# design.net
KiCad netlist of a schematic drawn in Altium Designer
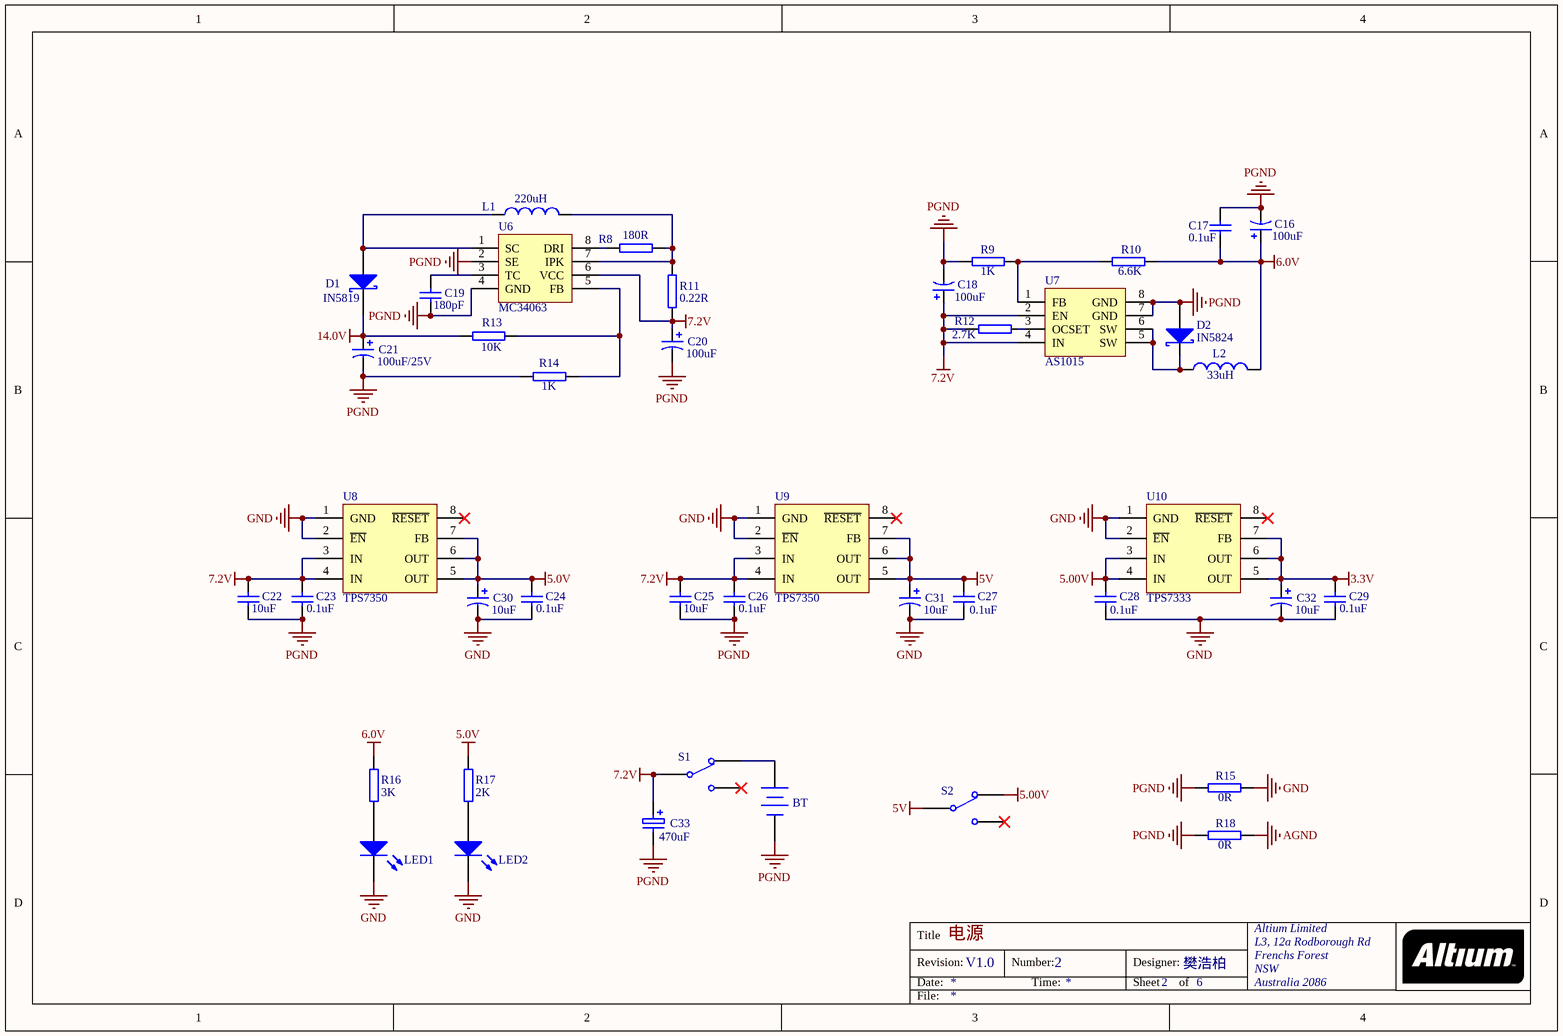
[diagram p0: 电源.SchDoc]

(export (version "E")
  (design (tool "Eeschema 10.0.6"))
  (components
    (comp (ref "BT")
      (value "Battery")
      (footprint "Header-5.0-SMD")
      (libsource (lib "Connectors") (part "Battery"))
    )
    (comp (ref "C16")
      (value "100uF")
      (footprint "CASE-C_6032-28")
      (libsource (lib "Connectors") (part "Cap-Pol_1"))
    )
    (comp (ref "C17") (value "0.1uF") (footprint "CAP-0603") (libsource (lib "Connectors") (part "Cap")))
    (comp (ref "C18")
      (value "100uF")
      (footprint "CASE-C_6032-28")
      (libsource (lib "Connectors") (part "Cap-Pol_1"))
    )
    (comp (ref "C19") (value "180pF") (footprint "CAP-0603") (libsource (lib "Connectors") (part "Cap")))
    (comp (ref "C20")
      (value "100uF")
      (footprint "CASE-C_6032-28")
      (libsource (lib "Connectors") (part "Cap-Pol_1"))
    )
    (comp (ref "C21")
      (value "100uF/25V")
      (footprint "CASE-D_7343-31")
      (libsource (lib "Connectors") (part "Cap-Pol_1"))
    )
    (comp (ref "C22") (value "10uF") (footprint "CAP-0603") (libsource (lib "Connectors") (part "Cap")))
    (comp (ref "C23") (value "0.1uF") (footprint "CAP-0603") (libsource (lib "Connectors") (part "Cap")))
    (comp (ref "C24") (value "0.1uF") (footprint "CAP-0603") (libsource (lib "Connectors") (part "Cap")))
    (comp (ref "C25") (value "10uF") (footprint "CAP-0603") (libsource (lib "Connectors") (part "Cap")))
    (comp (ref "C26") (value "0.1uF") (footprint "CAP-0603") (libsource (lib "Connectors") (part "Cap")))
    (comp (ref "C27") (value "0.1uF") (footprint "CAP-0603") (libsource (lib "Connectors") (part "Cap")))
    (comp (ref "C28") (value "0.1uF") (footprint "CAP-0603") (libsource (lib "Connectors") (part "Cap")))
    (comp (ref "C29") (value "0.1uF") (footprint "CAP-0603") (libsource (lib "Connectors") (part "Cap")))
    (comp (ref "C30")
      (value "10uF")
      (footprint "CASE-A_3216-18")
      (libsource (lib "Connectors") (part "Cap-Pol_1"))
    )
    (comp (ref "C31")
      (value "10uF")
      (footprint "CASE-A_3216-18")
      (libsource (lib "Connectors") (part "Cap-Pol_1"))
    )
    (comp (ref "C32")
      (value "10uF")
      (footprint "CASE-A_3216-18")
      (libsource (lib "Connectors") (part "Cap-Pol_1"))
    )
    (comp (ref "C33")
      (value "470uF")
      (footprint "CAP-ALU-F_8.0x8.3x10.2")
      (libsource (lib "Connectors") (part "Cap-Pol_2"))
    )
    (comp (ref "D1")
      (value "IN5819")
      (footprint "Diode-SMD-SOD-123")
      (libsource (lib "Connectors") (part "Diode-Schottky"))
    )
    (comp (ref "D2")
      (value "IN5824")
      (footprint "Diode-SMD-SMA")
      (libsource (lib "Connectors") (part "Diode-Schottky"))
    )
    (comp (ref "L1")
      (value "220uH")
      (footprint "Inductor-CD-54")
      (libsource (lib "Connectors") (part "Inductor"))
    )
    (comp (ref "L2")
      (value "33uH")
      (footprint "Inductor-CD-54")
      (libsource (lib "Connectors") (part "Inductor"))
    )
    (comp (ref "LED1") (value "LED") (footprint "LED-GRE-0603") (libsource (lib "Connectors") (part "LED")))
    (comp (ref "LED2") (value "LED") (footprint "LED-BLU-0603") (libsource (lib "Connectors") (part "LED")))
    (comp (ref "R8") (value "180R") (footprint "RES-0603") (libsource (lib "Connectors") (part "Res")))
    (comp (ref "R9") (value "1K") (footprint "RES-0603") (libsource (lib "Connectors") (part "Res")))
    (comp (ref "R10") (value "6.6K") (footprint "RES-0603") (libsource (lib "Connectors") (part "Res")))
    (comp (ref "R11") (value "0.22R") (footprint "RES-0603") (libsource (lib "Connectors") (part "Res")))
    (comp (ref "R12") (value "2.7K") (footprint "RES-0603") (libsource (lib "Connectors") (part "Res")))
    (comp (ref "R13") (value "10K") (footprint "RES-0603") (libsource (lib "Connectors") (part "Res")))
    (comp (ref "R14") (value "1K") (footprint "RES-0603") (libsource (lib "Connectors") (part "Res")))
    (comp (ref "R15") (value "0R") (footprint "RES-0603") (libsource (lib "Connectors") (part "Res")))
    (comp (ref "R16") (value "3K") (footprint "RES-0603") (libsource (lib "Connectors") (part "Res")))
    (comp (ref "R17") (value "2K") (footprint "RES-0603") (libsource (lib "Connectors") (part "Res")))
    (comp (ref "R18") (value "0R") (footprint "RES-0603") (libsource (lib "Connectors") (part "Res")))
    (comp (ref "S1")
      (value "Key-3")
      (footprint "SW-3-SMTS-102")
      (libsource (lib "Connectors") (part "Key-3"))
    )
    (comp (ref "S2")
      (value "Key-3")
      (footprint "SW-3-SMTS-102")
      (libsource (lib "Connectors") (part "Key-3"))
    )
    (comp (ref "U6") (value "MC34063") (footprint "SOP-8") (libsource (lib "Devices") (part "MC34063")))
    (comp (ref "U7") (value "AS1015") (footprint "SOP-8") (libsource (lib "Devices") (part "AS1015")))
    (comp (ref "U8") (value "TPS7350") (footprint "SOP-8") (libsource (lib "Devices") (part "TPS7350")))
    (comp (ref "U9") (value "TPS7350") (footprint "SOP-8") (libsource (lib "Devices") (part "TPS7350")))
    (comp (ref "U10") (value "TPS7333") (footprint "SOP-8") (libsource (lib "Devices") (part "TPS7350")))
  )
  (nets
    (net (code "1") (name "3.3V") (class "Default")
      (node (ref "C29") (pin "2") (pinfunction "2_2") (pintype "passive"))
      (node (ref "C32") (pin "A") (pinfunction "A_A") (pintype "passive"))
      (node (ref "U10") (pin "5") (pinfunction "OUT_5") (pintype "power_in"))
      (node (ref "U10") (pin "6") (pinfunction "OUT_6") (pintype "power_in"))
      (node (ref "U10") (pin "7") (pinfunction "FB_7") (pintype "power_in"))
    )
    (net (code "2") (name "5.00V") (class "Default")
      (node (ref "C28") (pin "2") (pinfunction "2_2") (pintype "passive"))
      (node (ref "S2") (pin "3") (pinfunction "3_3") (pintype "passive"))
      (node (ref "U10") (pin "3") (pinfunction "IN_3") (pintype "power_in"))
      (node (ref "U10") (pin "4") (pinfunction "IN_4") (pintype "power_in"))
    )
    (net (code "3") (name "5.0V") (class "Default")
      (node (ref "C24") (pin "2") (pinfunction "2_2") (pintype "passive"))
      (node (ref "C30") (pin "A") (pinfunction "A_A") (pintype "passive"))
      (node (ref "R17") (pin "2") (pinfunction "2_2") (pintype "passive"))
      (node (ref "U8") (pin "5") (pinfunction "OUT_5") (pintype "power_in"))
      (node (ref "U8") (pin "6") (pinfunction "OUT_6") (pintype "power_in"))
      (node (ref "U8") (pin "7") (pinfunction "FB_7") (pintype "power_in"))
    )
    (net (code "4") (name "5V") (class "Default")
      (node (ref "C27") (pin "2") (pinfunction "2_2") (pintype "passive"))
      (node (ref "C31") (pin "A") (pinfunction "A_A") (pintype "passive"))
      (node (ref "S2") (pin "2") (pinfunction "2_2") (pintype "passive"))
      (node (ref "U9") (pin "5") (pinfunction "OUT_5") (pintype "power_in"))
      (node (ref "U9") (pin "6") (pinfunction "OUT_6") (pintype "power_in"))
      (node (ref "U9") (pin "7") (pinfunction "FB_7") (pintype "power_in"))
    )
    (net (code "5") (name "6.0V") (class "Default")
      (node (ref "C16") (pin "A") (pinfunction "A_A") (pintype "passive"))
      (node (ref "C17") (pin "1") (pinfunction "1_1") (pintype "passive"))
      (node (ref "L2") (pin "2") (pinfunction "2_2") (pintype "passive"))
      (node (ref "R10") (pin "1") (pinfunction "1_1") (pintype "passive"))
      (node (ref "R16") (pin "2") (pinfunction "2_2") (pintype "passive"))
    )
    (net (code "6") (name "7.2V") (class "Default")
      (node (ref "C18") (pin "A") (pinfunction "A_A") (pintype "passive"))
      (node (ref "C20") (pin "A") (pinfunction "A_A") (pintype "passive"))
      (node (ref "C22") (pin "2") (pinfunction "2_2") (pintype "passive"))
      (node (ref "C23") (pin "2") (pinfunction "2_2") (pintype "passive"))
      (node (ref "C25") (pin "2") (pinfunction "2_2") (pintype "passive"))
      (node (ref "C26") (pin "2") (pinfunction "2_2") (pintype "passive"))
      (node (ref "C33") (pin "A") (pinfunction "A_A") (pintype "passive"))
      (node (ref "R11") (pin "1") (pinfunction "1_1") (pintype "passive"))
      (node (ref "R12") (pin "2") (pinfunction "2_2") (pintype "passive"))
      (node (ref "S1") (pin "2") (pinfunction "2_2") (pintype "passive"))
      (node (ref "U6") (pin "6") (pinfunction "VCC_6") (pintype "passive"))
      (node (ref "U7") (pin "2") (pinfunction "EN_2") (pintype "passive"))
      (node (ref "U7") (pin "4") (pinfunction "IN_4") (pintype "passive"))
      (node (ref "U8") (pin "3") (pinfunction "IN_3") (pintype "power_in"))
      (node (ref "U8") (pin "4") (pinfunction "IN_4") (pintype "power_in"))
      (node (ref "U9") (pin "3") (pinfunction "IN_3") (pintype "power_in"))
      (node (ref "U9") (pin "4") (pinfunction "IN_4") (pintype "power_in"))
    )
    (net (code "7") (name "14.0V") (class "Default")
      (node (ref "C21") (pin "A") (pinfunction "A_A") (pintype "passive"))
      (node (ref "D1") (pin "K") (pinfunction "K_K") (pintype "passive"))
      (node (ref "R13") (pin "1") (pinfunction "1_1") (pintype "passive"))
    )
    (net (code "8") (name "AGND") (class "Default")
      (node (ref "R18") (pin "1") (pinfunction "1_1") (pintype "passive"))
    )
    (net (code "9") (name "GND") (class "Default")
      (node (ref "C24") (pin "1") (pinfunction "1_1") (pintype "passive"))
      (node (ref "C27") (pin "1") (pinfunction "1_1") (pintype "passive"))
      (node (ref "C28") (pin "1") (pinfunction "1_1") (pintype "passive"))
      (node (ref "C29") (pin "1") (pinfunction "1_1") (pintype "passive"))
      (node (ref "C30") (pin "K") (pinfunction "K_K") (pintype "passive"))
      (node (ref "C31") (pin "K") (pinfunction "K_K") (pintype "passive"))
      (node (ref "C32") (pin "K") (pinfunction "K_K") (pintype "passive"))
      (node (ref "LED1") (pin "K") (pinfunction "2_K") (pintype "passive"))
      (node (ref "LED2") (pin "K") (pinfunction "2_K") (pintype "passive"))
      (node (ref "R15") (pin "1") (pinfunction "1_1") (pintype "passive"))
      (node (ref "U10") (pin "1") (pinfunction "GND_1") (pintype "power_in"))
      (node (ref "U10") (pin "2") (pinfunction "~{EN}_2") (pintype "power_in"))
      (node (ref "U8") (pin "1") (pinfunction "GND_1") (pintype "power_in"))
      (node (ref "U8") (pin "2") (pinfunction "~{EN}_2") (pintype "power_in"))
      (node (ref "U9") (pin "1") (pinfunction "GND_1") (pintype "power_in"))
      (node (ref "U9") (pin "2") (pinfunction "~{EN}_2") (pintype "power_in"))
    )
    (net (code "10") (name "Net-(BT-+)") (class "Default")
      (node (ref "BT") (pin "1") (pinfunction "+_1") (pintype "passive"))
      (node (ref "S1") (pin "3") (pinfunction "3_3") (pintype "passive"))
    )
    (net (code "11") (name "Net-(D2-PadK)") (class "Default")
      (node (ref "D2") (pin "K") (pinfunction "K_K") (pintype "passive"))
      (node (ref "L2") (pin "1") (pinfunction "1_1") (pintype "passive"))
      (node (ref "U7") (pin "5") (pinfunction "SW_5") (pintype "passive"))
      (node (ref "U7") (pin "6") (pinfunction "SW_6") (pintype "passive"))
    )
    (net (code "12") (name "Net-(LED1-1)") (class "Default")
      (node (ref "LED1") (pin "A") (pinfunction "1_A") (pintype "passive"))
      (node (ref "R16") (pin "1") (pinfunction "1_1") (pintype "passive"))
    )
    (net (code "13") (name "Net-(LED2-1)") (class "Default")
      (node (ref "LED2") (pin "A") (pinfunction "1_A") (pintype "passive"))
      (node (ref "R17") (pin "1") (pinfunction "1_1") (pintype "passive"))
    )
    (net (code "14") (name "Net-(U6-DRI)") (class "Default")
      (node (ref "R8") (pin "1") (pinfunction "1_1") (pintype "passive"))
      (node (ref "U6") (pin "8") (pinfunction "DRI_8") (pintype "passive"))
    )
    (net (code "15") (name "Net-(U6-FB)") (class "Default")
      (node (ref "R13") (pin "2") (pinfunction "2_2") (pintype "passive"))
      (node (ref "R14") (pin "1") (pinfunction "1_1") (pintype "passive"))
      (node (ref "U6") (pin "5") (pinfunction "FB_5") (pintype "passive"))
    )
    (net (code "16") (name "Net-(U6-IPK)") (class "Default")
      (node (ref "L1") (pin "2") (pinfunction "2_2") (pintype "passive"))
      (node (ref "R11") (pin "2") (pinfunction "2_2") (pintype "passive"))
      (node (ref "R8") (pin "2") (pinfunction "2_2") (pintype "passive"))
      (node (ref "U6") (pin "7") (pinfunction "IPK_7") (pintype "passive"))
    )
    (net (code "17") (name "Net-(U6-SC)") (class "Default")
      (node (ref "D1") (pin "A") (pinfunction "A_A") (pintype "passive"))
      (node (ref "L1") (pin "1") (pinfunction "1_1") (pintype "passive"))
      (node (ref "U6") (pin "1") (pinfunction "SC_1") (pintype "passive"))
    )
    (net (code "18") (name "Net-(U6-TC)") (class "Default")
      (node (ref "C19") (pin "2") (pinfunction "2_2") (pintype "passive"))
      (node (ref "U6") (pin "3") (pinfunction "TC_3") (pintype "passive"))
    )
    (net (code "19") (name "Net-(U7-FB)") (class "Default")
      (node (ref "R10") (pin "2") (pinfunction "2_2") (pintype "passive"))
      (node (ref "R9") (pin "2") (pinfunction "2_2") (pintype "passive"))
      (node (ref "U7") (pin "1") (pinfunction "FB_1") (pintype "passive"))
    )
    (net (code "20") (name "Net-(U7-OCSET)") (class "Default")
      (node (ref "R12") (pin "1") (pinfunction "1_1") (pintype "passive"))
      (node (ref "U7") (pin "3") (pinfunction "OCSET_3") (pintype "passive"))
    )
    (net (code "21") (name "PGND") (class "Default")
      (node (ref "BT") (pin "2") (pinfunction "-_2") (pintype "passive"))
      (node (ref "C16") (pin "K") (pinfunction "K_K") (pintype "passive"))
      (node (ref "C17") (pin "2") (pinfunction "2_2") (pintype "passive"))
      (node (ref "C18") (pin "K") (pinfunction "K_K") (pintype "passive"))
      (node (ref "C19") (pin "1") (pinfunction "1_1") (pintype "passive"))
      (node (ref "C20") (pin "K") (pinfunction "K_K") (pintype "passive"))
      (node (ref "C21") (pin "K") (pinfunction "K_K") (pintype "passive"))
      (node (ref "C22") (pin "1") (pinfunction "1_1") (pintype "passive"))
      (node (ref "C23") (pin "1") (pinfunction "1_1") (pintype "passive"))
      (node (ref "C25") (pin "1") (pinfunction "1_1") (pintype "passive"))
      (node (ref "C26") (pin "1") (pinfunction "1_1") (pintype "passive"))
      (node (ref "C33") (pin "K") (pinfunction "K_K") (pintype "passive"))
      (node (ref "D2") (pin "A") (pinfunction "A_A") (pintype "passive"))
      (node (ref "R14") (pin "2") (pinfunction "2_2") (pintype "passive"))
      (node (ref "R15") (pin "2") (pinfunction "2_2") (pintype "passive"))
      (node (ref "R18") (pin "2") (pinfunction "2_2") (pintype "passive"))
      (node (ref "R9") (pin "1") (pinfunction "1_1") (pintype "passive"))
      (node (ref "U6") (pin "2") (pinfunction "SE_2") (pintype "passive"))
      (node (ref "U6") (pin "4") (pinfunction "GND_4") (pintype "passive"))
      (node (ref "U7") (pin "7") (pinfunction "GND_7") (pintype "passive"))
      (node (ref "U7") (pin "8") (pinfunction "GND_8") (pintype "passive"))
    )
    (net (code "22") (name "unconnected-(S1-Pad1)") (class "Default")
      (node (ref "S1") (pin "1") (pinfunction "1_1") (pintype "passive+no_connect"))
    )
    (net (code "23") (name "unconnected-(S2-Pad1)") (class "Default")
      (node (ref "S2") (pin "1") (pinfunction "1_1") (pintype "passive+no_connect"))
    )
    (net (code "24") (name "unconnected-(U8-~{RESET}-Pad8)") (class "Default")
      (node (ref "U8") (pin "8") (pinfunction "~{RESET}_8") (pintype "power_in+no_connect"))
    )
    (net (code "25") (name "unconnected-(U9-~{RESET}-Pad8)") (class "Default")
      (node (ref "U9") (pin "8") (pinfunction "~{RESET}_8") (pintype "power_in+no_connect"))
    )
    (net (code "26") (name "unconnected-(U10-~{RESET}-Pad8)") (class "Default")
      (node (ref "U10") (pin "8") (pinfunction "~{RESET}_8") (pintype "power_in+no_connect"))
    )
  )
)
